# shield.net
KiCad netlist of a schematic drawn in EAGLE
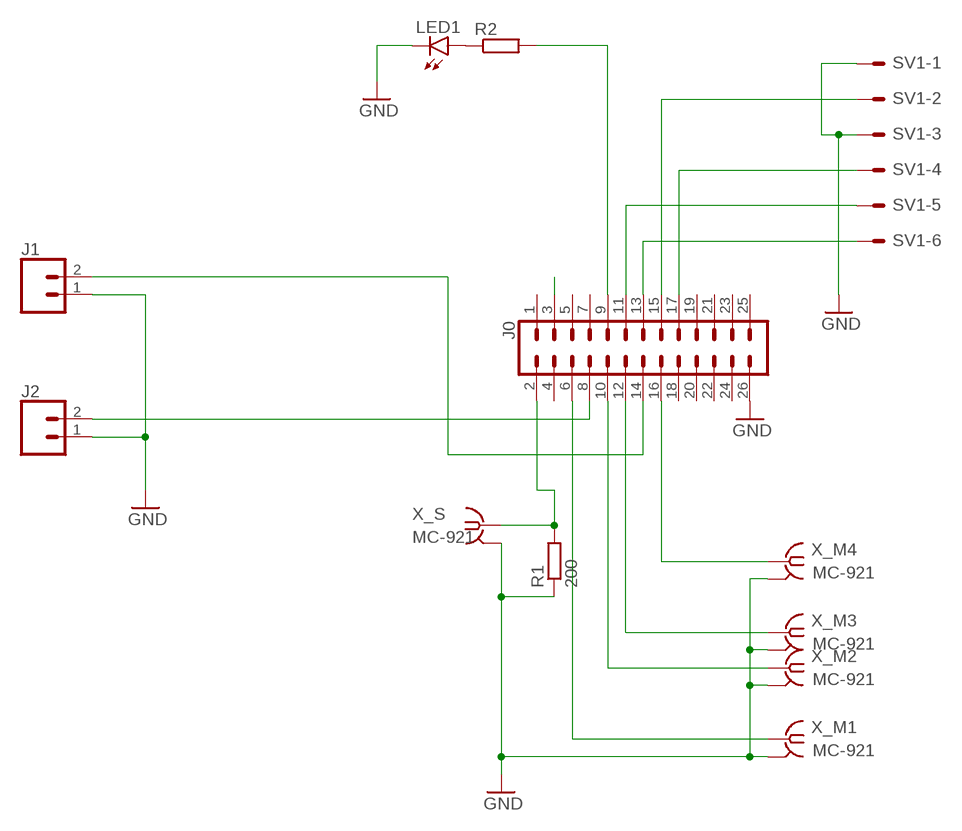
[diagram p0: schematic, sheet 1]

(export (version "E")
  (design (tool "Eeschema 10.0.6"))
  (components
    (comp (ref "J0")
      (value "CONN_13X22X13")
      (footprint "eagle-import:2X13")
      (libsource (lib "eagle-import") (part "CONN_13X22X13"))
    )
    (comp (ref "J1")
      (value "CONN_02")
      (footprint "eagle-import:1X02")
      (libsource (lib "eagle-import") (part "CONN_02"))
    )
    (comp (ref "J2")
      (value "CONN_02")
      (footprint "eagle-import:1X02")
      (libsource (lib "eagle-import") (part "CONN_02"))
    )
    (comp (ref "LED1")
      (value "LEDCHIPLED_0805")
      (footprint "eagle-import:CHIPLED_0805")
      (libsource (lib "eagle-import") (part "LEDCHIPLED_0805"))
    )
    (comp (ref "R1")
      (value "200")
      (footprint "eagle-import:R0805")
      (libsource (lib "eagle-import") (part "R-EU_R0805"))
    )
    (comp (ref "R2")
      (value "R-EU_R0805")
      (footprint "eagle-import:R0805")
      (libsource (lib "eagle-import") (part "R-EU_R0805"))
    )
    (comp (ref "SV1")
      (value "ML6E")
      (footprint "eagle-import:ML6")
      (libsource (lib "eagle-import") (part "ML6E"))
    )
    (comp (ref "X_M1")
      (value "MC-921")
      (footprint "eagle-import:MC-921")
      (libsource (lib "eagle-import") (part "MC-921"))
    )
    (comp (ref "X_M2")
      (value "MC-921")
      (footprint "eagle-import:MC-921")
      (libsource (lib "eagle-import") (part "MC-921"))
    )
    (comp (ref "X_M3")
      (value "MC-921")
      (footprint "eagle-import:MC-921")
      (libsource (lib "eagle-import") (part "MC-921"))
    )
    (comp (ref "X_M4")
      (value "MC-921")
      (footprint "eagle-import:MC-921")
      (libsource (lib "eagle-import") (part "MC-921"))
    )
    (comp (ref "X_S")
      (value "MC-921")
      (footprint "eagle-import:MC-921")
      (libsource (lib "eagle-import") (part "MC-921"))
    )
  )
  (nets
    (net (code "1") (name "GND") (class "Default")
      (node (ref "J0") (pin "26") (pinfunction "26_26") (pintype "passive"))
      (node (ref "J1") (pin "1") (pinfunction "1_1") (pintype "passive"))
      (node (ref "J2") (pin "1") (pinfunction "1_1") (pintype "passive"))
      (node (ref "LED1") (pin "C") (pinfunction "C_C") (pintype "passive"))
      (node (ref "R1") (pin "1") (pinfunction "1_1") (pintype "passive"))
      (node (ref "SV1") (pin "1") (pinfunction "S_1") (pintype "passive"))
      (node (ref "SV1") (pin "3") (pinfunction "S_3") (pintype "passive"))
      (node (ref "X_M1") (pin "2@1") (pinfunction "GND_2@1") (pintype "passive"))
      (node (ref "X_M1") (pin "2@2") (pinfunction "GND_2@2") (pintype "passive"))
      (node (ref "X_M2") (pin "2@1") (pinfunction "GND_2@1") (pintype "passive"))
      (node (ref "X_M2") (pin "2@2") (pinfunction "GND_2@2") (pintype "passive"))
      (node (ref "X_M3") (pin "2@1") (pinfunction "GND_2@1") (pintype "passive"))
      (node (ref "X_M3") (pin "2@2") (pinfunction "GND_2@2") (pintype "passive"))
      (node (ref "X_M4") (pin "2@1") (pinfunction "GND_2@1") (pintype "passive"))
      (node (ref "X_M4") (pin "2@2") (pinfunction "GND_2@2") (pintype "passive"))
      (node (ref "X_S") (pin "2@1") (pinfunction "GND_2@1") (pintype "passive"))
      (node (ref "X_S") (pin "2@2") (pinfunction "GND_2@2") (pintype "passive"))
    )
    (net (code "2") (name "Net-(J0-Pad2)") (class "Default")
      (node (ref "J0") (pin "2") (pinfunction "2_2") (pintype "passive"))
      (node (ref "R1") (pin "2") (pinfunction "2_2") (pintype "passive"))
      (node (ref "X_S") (pin "1") (pinfunction "1_1") (pintype "passive"))
    )
    (net (code "3") (name "Net-(J0-Pad6)") (class "Default")
      (node (ref "J0") (pin "6") (pinfunction "6_6") (pintype "passive"))
      (node (ref "X_M1") (pin "1") (pinfunction "1_1") (pintype "passive"))
    )
    (net (code "4") (name "Net-(J0-Pad8)") (class "Default")
      (node (ref "J0") (pin "8") (pinfunction "8_8") (pintype "passive"))
      (node (ref "J2") (pin "2") (pinfunction "2_2") (pintype "passive"))
    )
    (net (code "5") (name "Net-(J0-Pad9)") (class "Default")
      (node (ref "J0") (pin "9") (pinfunction "9_9") (pintype "passive"))
      (node (ref "R2") (pin "2") (pinfunction "2_2") (pintype "passive"))
    )
    (net (code "6") (name "Net-(J0-Pad10)") (class "Default")
      (node (ref "J0") (pin "10") (pinfunction "10_10") (pintype "passive"))
      (node (ref "X_M2") (pin "1") (pinfunction "1_1") (pintype "passive"))
    )
    (net (code "7") (name "Net-(J0-Pad12)") (class "Default")
      (node (ref "J0") (pin "12") (pinfunction "12_12") (pintype "passive"))
      (node (ref "X_M3") (pin "1") (pinfunction "1_1") (pintype "passive"))
    )
    (net (code "8") (name "Net-(J0-Pad14)") (class "Default")
      (node (ref "J0") (pin "14") (pinfunction "14_14") (pintype "passive"))
      (node (ref "J1") (pin "2") (pinfunction "2_2") (pintype "passive"))
    )
    (net (code "9") (name "Net-(J0-Pad16)") (class "Default")
      (node (ref "J0") (pin "16") (pinfunction "16_16") (pintype "passive"))
      (node (ref "X_M4") (pin "1") (pinfunction "1_1") (pintype "passive"))
    )
    (net (code "10") (name "Net-(LED1-PadA)") (class "Default")
      (node (ref "LED1") (pin "A") (pinfunction "A_A") (pintype "passive"))
      (node (ref "R2") (pin "1") (pinfunction "1_1") (pintype "passive"))
    )
    (net (code "11") (name "Net-(SV1B-S)") (class "Default")
      (node (ref "J0") (pin "15") (pinfunction "15_15") (pintype "passive"))
      (node (ref "SV1") (pin "2") (pinfunction "S_2") (pintype "passive"))
    )
    (net (code "12") (name "Net-(SV1D-S)") (class "Default")
      (node (ref "J0") (pin "17") (pinfunction "17_17") (pintype "passive"))
      (node (ref "SV1") (pin "4") (pinfunction "S_4") (pintype "passive"))
    )
    (net (code "13") (name "Net-(SV1E-S)") (class "Default")
      (node (ref "J0") (pin "11") (pinfunction "11_11") (pintype "passive"))
      (node (ref "SV1") (pin "5") (pinfunction "S_5") (pintype "passive"))
    )
    (net (code "14") (name "Net-(SV1F-S)") (class "Default")
      (node (ref "J0") (pin "13") (pinfunction "13_13") (pintype "passive"))
      (node (ref "SV1") (pin "6") (pinfunction "S_6") (pintype "passive"))
    )
    (net (code "15") (name "unconnected-(J0-Pad1)") (class "Default")
      (node (ref "J0") (pin "1") (pinfunction "1_1") (pintype "passive"))
    )
    (net (code "16") (name "unconnected-(J0-Pad3)") (class "Default")
      (node (ref "J0") (pin "3") (pinfunction "3_3") (pintype "passive"))
    )
    (net (code "17") (name "unconnected-(J0-Pad4)") (class "Default")
      (node (ref "J0") (pin "4") (pinfunction "4_4") (pintype "passive"))
    )
    (net (code "18") (name "unconnected-(J0-Pad5)") (class "Default")
      (node (ref "J0") (pin "5") (pinfunction "5_5") (pintype "passive"))
    )
    (net (code "19") (name "unconnected-(J0-Pad7)") (class "Default")
      (node (ref "J0") (pin "7") (pinfunction "7_7") (pintype "passive"))
    )
    (net (code "20") (name "unconnected-(J0-Pad18)") (class "Default")
      (node (ref "J0") (pin "18") (pinfunction "18_18") (pintype "passive"))
    )
    (net (code "21") (name "unconnected-(J0-Pad19)") (class "Default")
      (node (ref "J0") (pin "19") (pinfunction "19_19") (pintype "passive"))
    )
    (net (code "22") (name "unconnected-(J0-Pad20)") (class "Default")
      (node (ref "J0") (pin "20") (pinfunction "20_20") (pintype "passive"))
    )
    (net (code "23") (name "unconnected-(J0-Pad21)") (class "Default")
      (node (ref "J0") (pin "21") (pinfunction "21_21") (pintype "passive"))
    )
    (net (code "24") (name "unconnected-(J0-Pad22)") (class "Default")
      (node (ref "J0") (pin "22") (pinfunction "22_22") (pintype "passive"))
    )
    (net (code "25") (name "unconnected-(J0-Pad23)") (class "Default")
      (node (ref "J0") (pin "23") (pinfunction "23_23") (pintype "passive"))
    )
    (net (code "26") (name "unconnected-(J0-Pad24)") (class "Default")
      (node (ref "J0") (pin "24") (pinfunction "24_24") (pintype "passive"))
    )
    (net (code "27") (name "unconnected-(J0-Pad25)") (class "Default")
      (node (ref "J0") (pin "25") (pinfunction "25_25") (pintype "passive"))
    )
  )
)
